# XplainedHorticulture.net
KiCad netlist of a schematic drawn in EAGLE
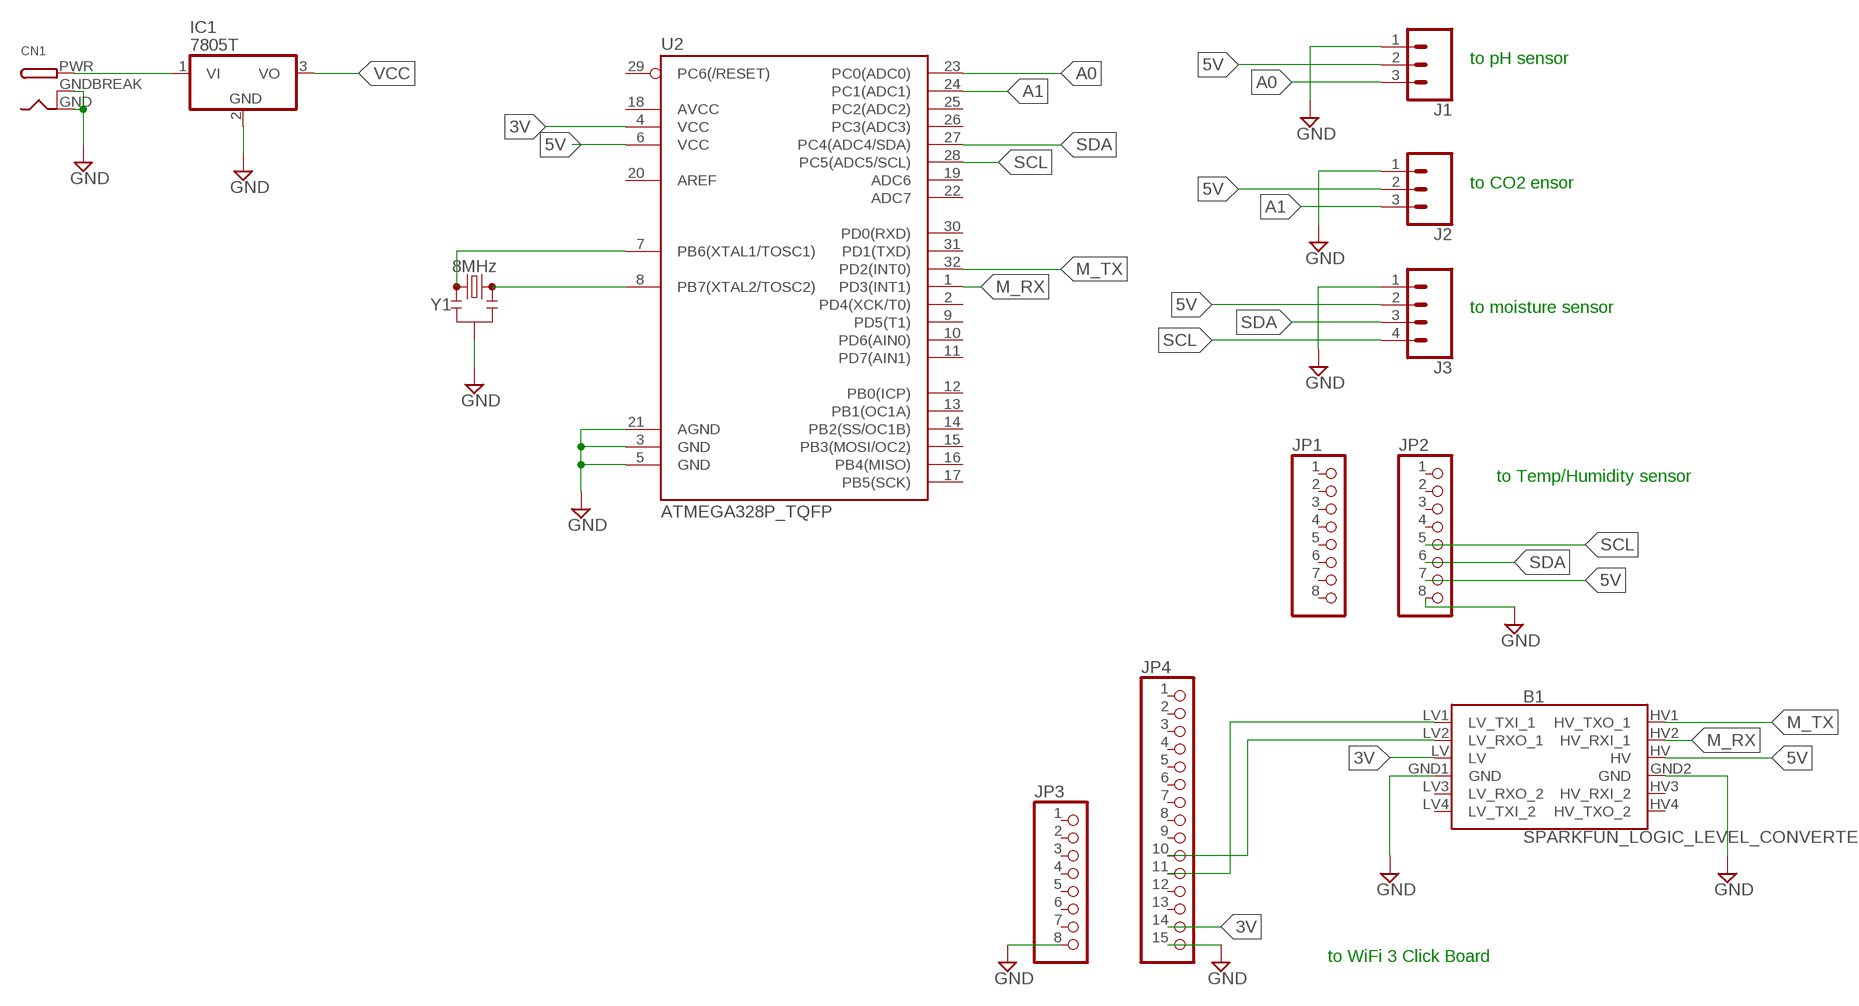
[diagram p0: schematic, sheet 1]

(export (version "E")
  (design (tool "Eeschema 10.0.6"))
  (components
    (comp (ref "B1")
      (value "SPARKFUN_LOGIC_LEVEL_CONVERTER")
      (footprint "eagle-import:SPARKFUN_LOGIC_LEVEL_CONVERTER")
      (libsource (lib "eagle-import") (part "SPARKFUN_LOGIC_LEVEL_CONVERTER"))
    )
    (comp (ref "CN1")
      (value "DCBARRELPTH")
      (footprint "eagle-import:DCJACK_2MM_PTH")
      (libsource (lib "eagle-import") (part "DCBARRELPTH"))
    )
    (comp (ref "IC1")
      (value "7805T")
      (footprint "eagle-import:TO220H")
      (libsource (lib "eagle-import") (part "78T05"))
    )
    (comp (ref "J1")
      (value "CONN_03JST-PTH")
      (footprint "eagle-import:JST-3-PTH")
      (libsource (lib "eagle-import") (part "CONN_03JST-PTH"))
    )
    (comp (ref "J2")
      (value "CONN_03JST-PTH")
      (footprint "eagle-import:JST-3-PTH")
      (libsource (lib "eagle-import") (part "CONN_03JST-PTH"))
    )
    (comp (ref "J3")
      (value "CONN_04JST-PTH")
      (footprint "eagle-import:JST-4-PTH")
      (libsource (lib "eagle-import") (part "CONN_04JST-PTH"))
    )
    (comp (ref "JP1")
      (value "PINHD-1X8BIG")
      (footprint "eagle-import:1X08-BIG")
      (libsource (lib "eagle-import") (part "PINHD-1X8BIG"))
    )
    (comp (ref "JP2")
      (value "PINHD-1X8BIG")
      (footprint "eagle-import:1X08-BIG")
      (libsource (lib "eagle-import") (part "PINHD-1X8BIG"))
    )
    (comp (ref "JP3")
      (value "PINHD-1X8BIG")
      (footprint "eagle-import:1X08-BIG")
      (libsource (lib "eagle-import") (part "PINHD-1X8BIG"))
    )
    (comp (ref "JP4")
      (value "PINHD-1X15-CB")
      (footprint "eagle-import:1X15-CB")
      (libsource (lib "eagle-import") (part "PINHD-1X15-CB"))
    )
    (comp (ref "U2")
      (value "ATMEGA328P_TQFP")
      (footprint "eagle-import:TQFP32-08")
      (libsource (lib "eagle-import") (part "ATMEGA328P_TQFP"))
    )
    (comp (ref "Y1")
      (value "8MHz")
      (footprint "eagle-import:RESONATOR-SMD-3.2X1.3")
      (libsource (lib "eagle-import") (part "RESONATOR-8MHZSMD_3.2X1.3"))
    )
  )
  (nets
    (net (code "1") (name "3V") (class "Default")
      (node (ref "B1") (pin "LV") (pinfunction "LV_LV") (pintype "power_in"))
      (node (ref "JP4") (pin "14") (pinfunction "14_14") (pintype "passive"))
      (node (ref "U2") (pin "4") (pinfunction "VCC_4") (pintype "bidirectional"))
    )
    (net (code "2") (name "5V") (class "Default")
      (node (ref "B1") (pin "HV") (pinfunction "HV_HV") (pintype "power_in"))
      (node (ref "J1") (pin "2") (pinfunction "2_2") (pintype "passive"))
      (node (ref "J2") (pin "2") (pinfunction "2_2") (pintype "passive"))
      (node (ref "J3") (pin "2") (pinfunction "2_2") (pintype "passive"))
      (node (ref "JP2") (pin "7") (pinfunction "7_7") (pintype "passive"))
      (node (ref "U2") (pin "6") (pinfunction "VCC_6") (pintype "bidirectional"))
    )
    (net (code "3") (name "A0") (class "Default")
      (node (ref "J1") (pin "3") (pinfunction "3_3") (pintype "passive"))
      (node (ref "U2") (pin "23") (pinfunction "PC0(ADC0)_23") (pintype "bidirectional"))
    )
    (net (code "4") (name "A1") (class "Default")
      (node (ref "J2") (pin "3") (pinfunction "3_3") (pintype "passive"))
      (node (ref "U2") (pin "24") (pinfunction "PC1(ADC1)_24") (pintype "bidirectional"))
    )
    (net (code "5") (name "GND") (class "Default")
      (node (ref "B1") (pin "GND1") (pinfunction "GND_GND1") (pintype "power_in"))
      (node (ref "B1") (pin "GND2") (pinfunction "GND_GND2") (pintype "power_in"))
      (node (ref "CN1") (pin "GND") (pinfunction "GND_GND") (pintype "power_in"))
      (node (ref "CN1") (pin "GNDBREAK") (pinfunction "GNDBREAK_GNDBREAK") (pintype "power_in"))
      (node (ref "IC1") (pin "2") (pinfunction "GND_2") (pintype "passive"))
      (node (ref "J1") (pin "1") (pinfunction "1_1") (pintype "passive"))
      (node (ref "J2") (pin "1") (pinfunction "1_1") (pintype "passive"))
      (node (ref "J3") (pin "1") (pinfunction "1_1") (pintype "passive"))
      (node (ref "JP2") (pin "8") (pinfunction "8_8") (pintype "passive"))
      (node (ref "JP3") (pin "8") (pinfunction "8_8") (pintype "passive"))
      (node (ref "JP4") (pin "15") (pinfunction "15_15") (pintype "passive"))
      (node (ref "U2") (pin "21") (pinfunction "AGND_21") (pintype "bidirectional"))
      (node (ref "U2") (pin "3") (pinfunction "GND_3") (pintype "bidirectional"))
      (node (ref "U2") (pin "5") (pinfunction "GND_5") (pintype "bidirectional"))
      (node (ref "Y1") (pin "2") (pinfunction "2_2") (pintype "passive"))
    )
    (net (code "6") (name "M_RX") (class "Default")
      (node (ref "B1") (pin "HV2") (pinfunction "HV_RXI_1_HV2") (pintype "bidirectional"))
      (node (ref "U2") (pin "1") (pinfunction "PD3(INT1)_1") (pintype "bidirectional"))
    )
    (net (code "7") (name "M_TX") (class "Default")
      (node (ref "B1") (pin "HV1") (pinfunction "HV_TXO_1_HV1") (pintype "bidirectional"))
      (node (ref "U2") (pin "32") (pinfunction "PD2(INT0)_32") (pintype "bidirectional"))
    )
    (net (code "8") (name "Net-(B1-LV_RXO_1)") (class "Default")
      (node (ref "B1") (pin "LV2") (pinfunction "LV_RXO_1_LV2") (pintype "bidirectional"))
      (node (ref "JP4") (pin "10") (pinfunction "10_10") (pintype "passive"))
    )
    (net (code "9") (name "Net-(B1-LV_TXI_1)") (class "Default")
      (node (ref "B1") (pin "LV1") (pinfunction "LV_TXI_1_LV1") (pintype "bidirectional"))
      (node (ref "JP4") (pin "11") (pinfunction "11_11") (pintype "passive"))
    )
    (net (code "10") (name "Net-(IC1-VI)") (class "Default")
      (node (ref "CN1") (pin "PWR") (pinfunction "PWR_PWR") (pintype "power_in"))
      (node (ref "IC1") (pin "1") (pinfunction "VI_1") (pintype "input"))
    )
    (net (code "11") (name "Net-(U2-PB6(XTAL1{slash}TOSC1))") (class "Default")
      (node (ref "U2") (pin "7") (pinfunction "PB6(XTAL1/TOSC1)_7") (pintype "bidirectional"))
      (node (ref "Y1") (pin "1") (pinfunction "1_1") (pintype "passive"))
    )
    (net (code "12") (name "Net-(U2-PB7(XTAL2{slash}TOSC2))") (class "Default")
      (node (ref "U2") (pin "8") (pinfunction "PB7(XTAL2/TOSC2)_8") (pintype "bidirectional"))
      (node (ref "Y1") (pin "3") (pinfunction "3_3") (pintype "passive"))
    )
    (net (code "13") (name "SCL") (class "Default")
      (node (ref "J3") (pin "4") (pinfunction "4_4") (pintype "passive"))
      (node (ref "JP2") (pin "5") (pinfunction "5_5") (pintype "passive"))
      (node (ref "U2") (pin "28") (pinfunction "PC5(ADC5/SCL)_28") (pintype "bidirectional"))
    )
    (net (code "14") (name "SDA") (class "Default")
      (node (ref "J3") (pin "3") (pinfunction "3_3") (pintype "passive"))
      (node (ref "JP2") (pin "6") (pinfunction "6_6") (pintype "passive"))
      (node (ref "U2") (pin "27") (pinfunction "PC4(ADC4/SDA)_27") (pintype "bidirectional"))
    )
    (net (code "15") (name "VCC") (class "Default")
      (node (ref "IC1") (pin "3") (pinfunction "VO_3") (pintype "passive"))
    )
    (net (code "16") (name "unconnected-(B1-HV_RXI_2-PadHV3)") (class "Default")
      (node (ref "B1") (pin "HV3") (pinfunction "HV_RXI_2_HV3") (pintype "bidirectional"))
    )
    (net (code "17") (name "unconnected-(B1-HV_TXO_2-PadHV4)") (class "Default")
      (node (ref "B1") (pin "HV4") (pinfunction "HV_TXO_2_HV4") (pintype "bidirectional"))
    )
    (net (code "18") (name "unconnected-(B1-LV_RXO_2-PadLV3)") (class "Default")
      (node (ref "B1") (pin "LV3") (pinfunction "LV_RXO_2_LV3") (pintype "bidirectional"))
    )
    (net (code "19") (name "unconnected-(B1-LV_TXI_2-PadLV4)") (class "Default")
      (node (ref "B1") (pin "LV4") (pinfunction "LV_TXI_2_LV4") (pintype "bidirectional"))
    )
    (net (code "20") (name "unconnected-(JP1-Pad1)") (class "Default")
      (node (ref "JP1") (pin "1") (pinfunction "1_1") (pintype "passive"))
    )
    (net (code "21") (name "unconnected-(JP1-Pad2)") (class "Default")
      (node (ref "JP1") (pin "2") (pinfunction "2_2") (pintype "passive"))
    )
    (net (code "22") (name "unconnected-(JP1-Pad3)") (class "Default")
      (node (ref "JP1") (pin "3") (pinfunction "3_3") (pintype "passive"))
    )
    (net (code "23") (name "unconnected-(JP1-Pad4)") (class "Default")
      (node (ref "JP1") (pin "4") (pinfunction "4_4") (pintype "passive"))
    )
    (net (code "24") (name "unconnected-(JP1-Pad5)") (class "Default")
      (node (ref "JP1") (pin "5") (pinfunction "5_5") (pintype "passive"))
    )
    (net (code "25") (name "unconnected-(JP1-Pad6)") (class "Default")
      (node (ref "JP1") (pin "6") (pinfunction "6_6") (pintype "passive"))
    )
    (net (code "26") (name "unconnected-(JP1-Pad7)") (class "Default")
      (node (ref "JP1") (pin "7") (pinfunction "7_7") (pintype "passive"))
    )
    (net (code "27") (name "unconnected-(JP1-Pad8)") (class "Default")
      (node (ref "JP1") (pin "8") (pinfunction "8_8") (pintype "passive"))
    )
    (net (code "28") (name "unconnected-(JP2-Pad1)") (class "Default")
      (node (ref "JP2") (pin "1") (pinfunction "1_1") (pintype "passive"))
    )
    (net (code "29") (name "unconnected-(JP2-Pad2)") (class "Default")
      (node (ref "JP2") (pin "2") (pinfunction "2_2") (pintype "passive"))
    )
    (net (code "30") (name "unconnected-(JP2-Pad3)") (class "Default")
      (node (ref "JP2") (pin "3") (pinfunction "3_3") (pintype "passive"))
    )
    (net (code "31") (name "unconnected-(JP2-Pad4)") (class "Default")
      (node (ref "JP2") (pin "4") (pinfunction "4_4") (pintype "passive"))
    )
    (net (code "32") (name "unconnected-(JP3-Pad1)") (class "Default")
      (node (ref "JP3") (pin "1") (pinfunction "1_1") (pintype "passive"))
    )
    (net (code "33") (name "unconnected-(JP3-Pad2)") (class "Default")
      (node (ref "JP3") (pin "2") (pinfunction "2_2") (pintype "passive"))
    )
    (net (code "34") (name "unconnected-(JP3-Pad3)") (class "Default")
      (node (ref "JP3") (pin "3") (pinfunction "3_3") (pintype "passive"))
    )
    (net (code "35") (name "unconnected-(JP3-Pad4)") (class "Default")
      (node (ref "JP3") (pin "4") (pinfunction "4_4") (pintype "passive"))
    )
    (net (code "36") (name "unconnected-(JP3-Pad5)") (class "Default")
      (node (ref "JP3") (pin "5") (pinfunction "5_5") (pintype "passive"))
    )
    (net (code "37") (name "unconnected-(JP3-Pad6)") (class "Default")
      (node (ref "JP3") (pin "6") (pinfunction "6_6") (pintype "passive"))
    )
    (net (code "38") (name "unconnected-(JP3-Pad7)") (class "Default")
      (node (ref "JP3") (pin "7") (pinfunction "7_7") (pintype "passive"))
    )
    (net (code "39") (name "unconnected-(JP4-Pad1)") (class "Default")
      (node (ref "JP4") (pin "1") (pinfunction "1_1") (pintype "passive"))
    )
    (net (code "40") (name "unconnected-(JP4-Pad2)") (class "Default")
      (node (ref "JP4") (pin "2") (pinfunction "2_2") (pintype "passive"))
    )
    (net (code "41") (name "unconnected-(JP4-Pad3)") (class "Default")
      (node (ref "JP4") (pin "3") (pinfunction "3_3") (pintype "passive"))
    )
    (net (code "42") (name "unconnected-(JP4-Pad4)") (class "Default")
      (node (ref "JP4") (pin "4") (pinfunction "4_4") (pintype "passive"))
    )
    (net (code "43") (name "unconnected-(JP4-Pad5)") (class "Default")
      (node (ref "JP4") (pin "5") (pinfunction "5_5") (pintype "passive"))
    )
    (net (code "44") (name "unconnected-(JP4-Pad6)") (class "Default")
      (node (ref "JP4") (pin "6") (pinfunction "6_6") (pintype "passive"))
    )
    (net (code "45") (name "unconnected-(JP4-Pad7)") (class "Default")
      (node (ref "JP4") (pin "7") (pinfunction "7_7") (pintype "passive"))
    )
    (net (code "46") (name "unconnected-(JP4-Pad8)") (class "Default")
      (node (ref "JP4") (pin "8") (pinfunction "8_8") (pintype "passive"))
    )
    (net (code "47") (name "unconnected-(JP4-Pad9)") (class "Default")
      (node (ref "JP4") (pin "9") (pinfunction "9_9") (pintype "passive"))
    )
    (net (code "48") (name "unconnected-(JP4-Pad12)") (class "Default")
      (node (ref "JP4") (pin "12") (pinfunction "12_12") (pintype "passive"))
    )
    (net (code "49") (name "unconnected-(JP4-Pad13)") (class "Default")
      (node (ref "JP4") (pin "13") (pinfunction "13_13") (pintype "passive"))
    )
    (net (code "50") (name "unconnected-(U2-ADC6-Pad19)") (class "Default")
      (node (ref "U2") (pin "19") (pinfunction "ADC6_19") (pintype "bidirectional"))
    )
    (net (code "51") (name "unconnected-(U2-ADC7-Pad22)") (class "Default")
      (node (ref "U2") (pin "22") (pinfunction "ADC7_22") (pintype "bidirectional"))
    )
    (net (code "52") (name "unconnected-(U2-AREF-Pad20)") (class "Default")
      (node (ref "U2") (pin "20") (pinfunction "AREF_20") (pintype "bidirectional"))
    )
    (net (code "53") (name "unconnected-(U2-AVCC-Pad18)") (class "Default")
      (node (ref "U2") (pin "18") (pinfunction "AVCC_18") (pintype "bidirectional"))
    )
    (net (code "54") (name "unconnected-(U2-PB0(ICP)-Pad12)") (class "Default")
      (node (ref "U2") (pin "12") (pinfunction "PB0(ICP)_12") (pintype "bidirectional"))
    )
    (net (code "55") (name "unconnected-(U2-PB1(OC1A)-Pad13)") (class "Default")
      (node (ref "U2") (pin "13") (pinfunction "PB1(OC1A)_13") (pintype "bidirectional"))
    )
    (net (code "56") (name "unconnected-(U2-PB2(SS{slash}OC1B)-Pad14)") (class "Default")
      (node (ref "U2") (pin "14") (pinfunction "PB2(SS/OC1B)_14") (pintype "bidirectional"))
    )
    (net (code "57") (name "unconnected-(U2-PB3(MOSI{slash}OC2)-Pad15)") (class "Default")
      (node (ref "U2") (pin "15") (pinfunction "PB3(MOSI/OC2)_15") (pintype "bidirectional"))
    )
    (net (code "58") (name "unconnected-(U2-PB4(MISO)-Pad16)") (class "Default")
      (node (ref "U2") (pin "16") (pinfunction "PB4(MISO)_16") (pintype "bidirectional"))
    )
    (net (code "59") (name "unconnected-(U2-PB5(SCK)-Pad17)") (class "Default")
      (node (ref "U2") (pin "17") (pinfunction "PB5(SCK)_17") (pintype "bidirectional"))
    )
    (net (code "60") (name "unconnected-(U2-PC2(ADC2)-Pad25)") (class "Default")
      (node (ref "U2") (pin "25") (pinfunction "PC2(ADC2)_25") (pintype "bidirectional"))
    )
    (net (code "61") (name "unconnected-(U2-PC3(ADC3)-Pad26)") (class "Default")
      (node (ref "U2") (pin "26") (pinfunction "PC3(ADC3)_26") (pintype "bidirectional"))
    )
    (net (code "62") (name "unconnected-(U2-PC6({slash}RESET)-Pad29)") (class "Default")
      (node (ref "U2") (pin "29") (pinfunction "PC6(/RESET)_29") (pintype "bidirectional"))
    )
    (net (code "63") (name "unconnected-(U2-PD0(RXD)-Pad30)") (class "Default")
      (node (ref "U2") (pin "30") (pinfunction "PD0(RXD)_30") (pintype "bidirectional"))
    )
    (net (code "64") (name "unconnected-(U2-PD1(TXD)-Pad31)") (class "Default")
      (node (ref "U2") (pin "31") (pinfunction "PD1(TXD)_31") (pintype "bidirectional"))
    )
    (net (code "65") (name "unconnected-(U2-PD4(XCK{slash}T0)-Pad2)") (class "Default")
      (node (ref "U2") (pin "2") (pinfunction "PD4(XCK/T0)_2") (pintype "bidirectional"))
    )
    (net (code "66") (name "unconnected-(U2-PD5(T1)-Pad9)") (class "Default")
      (node (ref "U2") (pin "9") (pinfunction "PD5(T1)_9") (pintype "bidirectional"))
    )
    (net (code "67") (name "unconnected-(U2-PD6(AIN0)-Pad10)") (class "Default")
      (node (ref "U2") (pin "10") (pinfunction "PD6(AIN0)_10") (pintype "bidirectional"))
    )
    (net (code "68") (name "unconnected-(U2-PD7(AIN1)-Pad11)") (class "Default")
      (node (ref "U2") (pin "11") (pinfunction "PD7(AIN1)_11") (pintype "bidirectional"))
    )
  )
)
